# tile.net
KiCad netlist of a schematic drawn in EAGLE
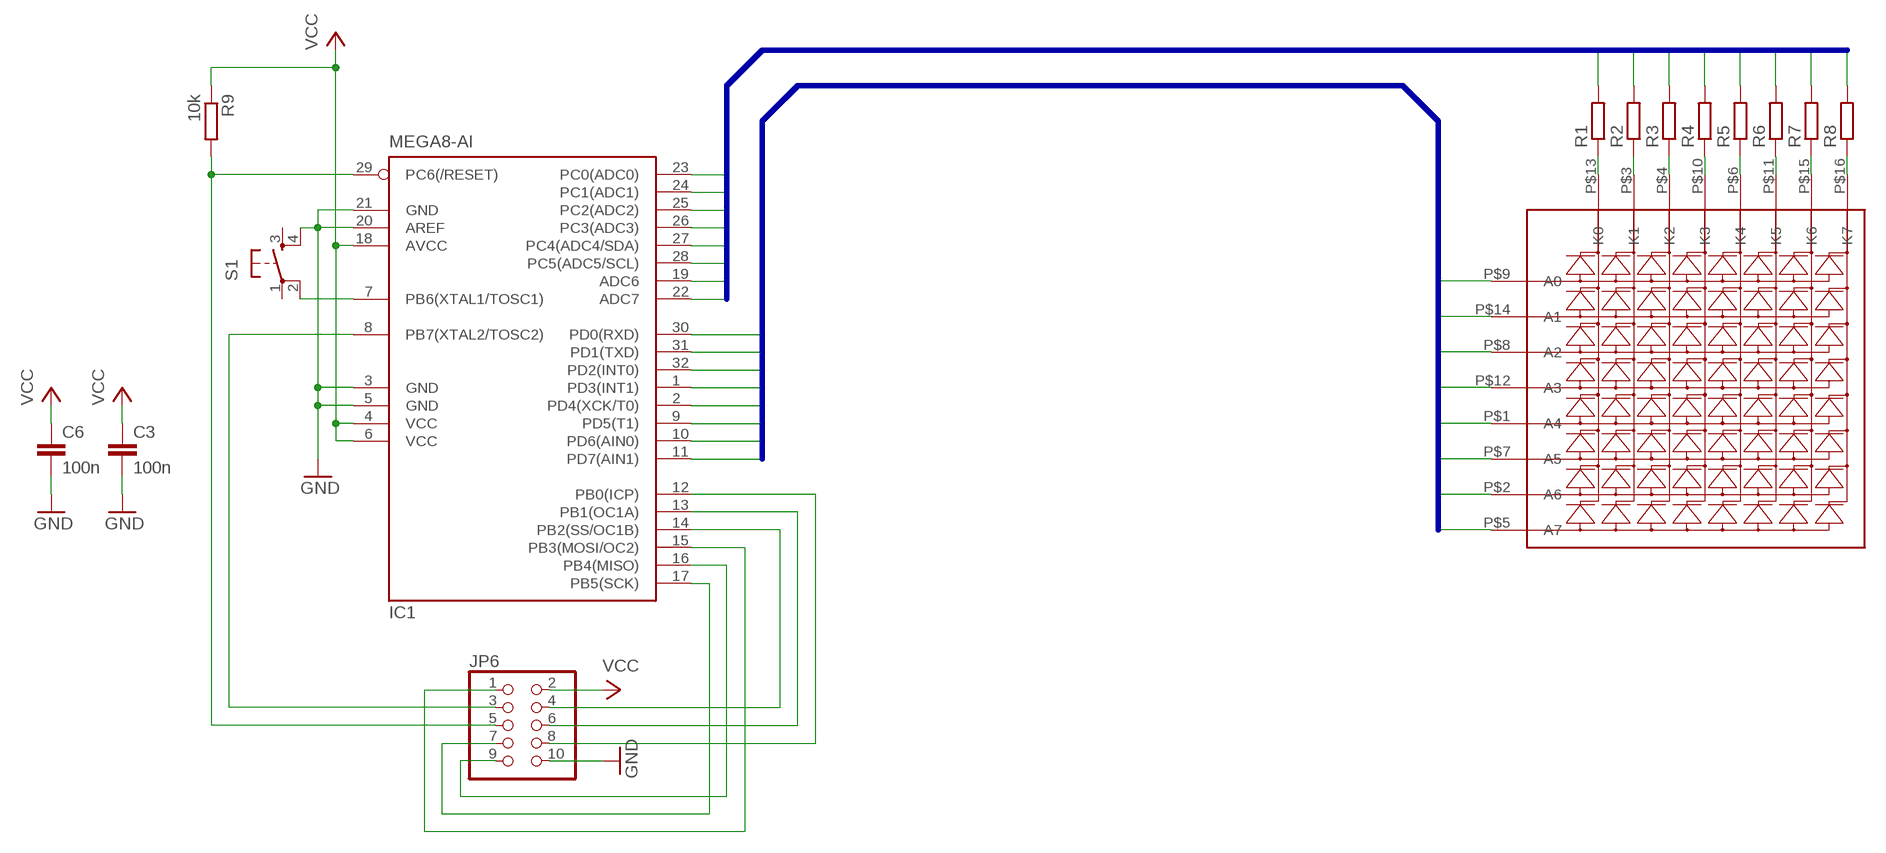
[diagram p0: schematic, sheet 1]
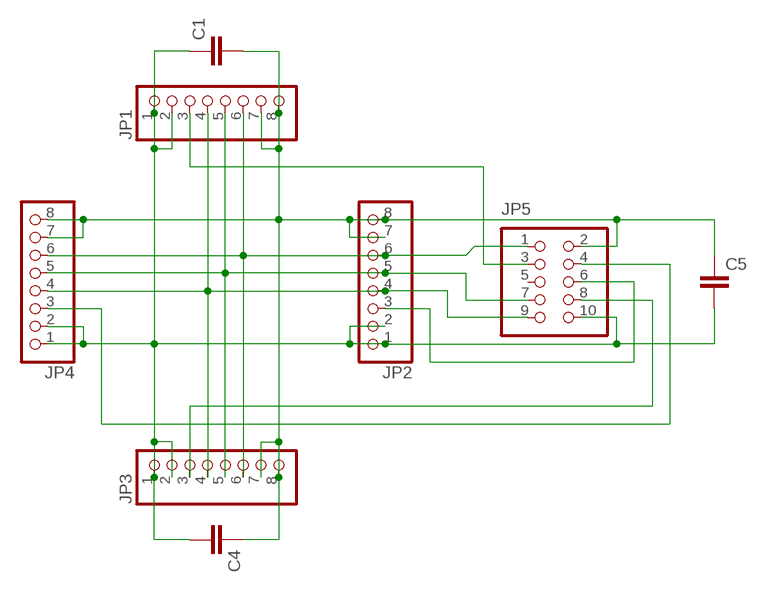
[diagram p1: schematic, sheet 2]

(export (version "E")
  (design (tool "Eeschema 10.0.6"))
  (components
    (comp (ref "C3")
      (value "100n")
      (footprint "eagle-import:C0805")
      (libsource (lib "eagle-import") (part "C-EUC0805"))
    )
    (comp (ref "C6")
      (value "100n")
      (footprint "eagle-import:C0805")
      (libsource (lib "eagle-import") (part "C-EUC0805"))
    )
    (comp (ref "IC1")
      (value "MEGA8-AI")
      (footprint "eagle-import:TQFP32-08")
      (libsource (lib "eagle-import") (part "MEGA8-AI"))
    )
    (comp (ref "JP6")
      (value "PINHD-2X5_2.54")
      (footprint "eagle-import:2X05")
      (libsource (lib "eagle-import") (part "PINHD-2X5_2.54"))
    )
    (comp (ref "R1")
      (value "R-EU_M0805")
      (footprint "eagle-import:M0805")
      (libsource (lib "eagle-import") (part "R-EU_M0805"))
    )
    (comp (ref "R2")
      (value "R-EU_M0805")
      (footprint "eagle-import:M0805")
      (libsource (lib "eagle-import") (part "R-EU_M0805"))
    )
    (comp (ref "R3")
      (value "R-EU_M0805")
      (footprint "eagle-import:M0805")
      (libsource (lib "eagle-import") (part "R-EU_M0805"))
    )
    (comp (ref "R4")
      (value "R-EU_M0805")
      (footprint "eagle-import:M0805")
      (libsource (lib "eagle-import") (part "R-EU_M0805"))
    )
    (comp (ref "R5")
      (value "R-EU_M0805")
      (footprint "eagle-import:M0805")
      (libsource (lib "eagle-import") (part "R-EU_M0805"))
    )
    (comp (ref "R6")
      (value "R-EU_M0805")
      (footprint "eagle-import:M0805")
      (libsource (lib "eagle-import") (part "R-EU_M0805"))
    )
    (comp (ref "R7")
      (value "R-EU_M0805")
      (footprint "eagle-import:M0805")
      (libsource (lib "eagle-import") (part "R-EU_M0805"))
    )
    (comp (ref "R8")
      (value "R-EU_M0805")
      (footprint "eagle-import:M0805")
      (libsource (lib "eagle-import") (part "R-EU_M0805"))
    )
    (comp (ref "R9")
      (value "10k")
      (footprint "eagle-import:M0805")
      (libsource (lib "eagle-import") (part "R-EU_M0805"))
    )
    (comp (ref "S1")
      (value "TAC_SWITCHSMD")
      (footprint "eagle-import:TACTILE_SWITCH_SMD")
      (libsource (lib "eagle-import") (part "TAC_SWITCHSMD"))
    )
    (comp (ref "U$1")
      (value "LED-MATRIX")
      (footprint "eagle-import:LED-MATRIX")
      (libsource (lib "eagle-import") (part "LED-MATRIX"))
    )
    (comp (ref "C1")
      (value "C-EUC0805")
      (footprint "eagle-import:C0805")
      (libsource (lib "eagle-import") (part "C-EUC0805"))
    )
    (comp (ref "C4")
      (value "C-EUC0805")
      (footprint "eagle-import:C0805")
      (libsource (lib "eagle-import") (part "C-EUC0805"))
    )
    (comp (ref "C5")
      (value "C-EUC0805")
      (footprint "eagle-import:C0805")
      (libsource (lib "eagle-import") (part "C-EUC0805"))
    )
    (comp (ref "JP1")
      (value "PINHD-1X8_2.00")
      (footprint "eagle-import:1X08M")
      (libsource (lib "eagle-import") (part "PINHD-1X8_2.00"))
    )
    (comp (ref "JP2")
      (value "PINHD-1X8_2.00")
      (footprint "eagle-import:1X08M")
      (libsource (lib "eagle-import") (part "PINHD-1X8_2.00"))
    )
    (comp (ref "JP3")
      (value "PINHD-1X8_2.00")
      (footprint "eagle-import:1X08M")
      (libsource (lib "eagle-import") (part "PINHD-1X8_2.00"))
    )
    (comp (ref "JP4")
      (value "PINHD-1X8_2.00")
      (footprint "eagle-import:1X08M")
      (libsource (lib "eagle-import") (part "PINHD-1X8_2.00"))
    )
    (comp (ref "JP5")
      (value "PINHD-2X5_2.54")
      (footprint "eagle-import:2X05")
      (libsource (lib "eagle-import") (part "PINHD-2X5_2.54"))
    )
  )
  (nets
    (net (code "1") (name "A0") (class "Default")
      (node (ref "IC1") (pin "30") (pinfunction "PD0(RXD)_30") (pintype "bidirectional"))
      (node (ref "U$1") (pin "P$9") (pinfunction "A0_P$9") (pintype "bidirectional"))
    )
    (net (code "2") (name "A1") (class "Default")
      (node (ref "IC1") (pin "31") (pinfunction "PD1(TXD)_31") (pintype "bidirectional"))
      (node (ref "U$1") (pin "P$14") (pinfunction "A1_P$14") (pintype "bidirectional"))
    )
    (net (code "3") (name "A2") (class "Default")
      (node (ref "IC1") (pin "32") (pinfunction "PD2(INT0)_32") (pintype "bidirectional"))
      (node (ref "U$1") (pin "P$8") (pinfunction "A2_P$8") (pintype "bidirectional"))
    )
    (net (code "4") (name "A3") (class "Default")
      (node (ref "IC1") (pin "1") (pinfunction "PD3(INT1)_1") (pintype "bidirectional"))
      (node (ref "U$1") (pin "P$12") (pinfunction "A3_P$12") (pintype "bidirectional"))
    )
    (net (code "5") (name "A4") (class "Default")
      (node (ref "IC1") (pin "2") (pinfunction "PD4(XCK/T0)_2") (pintype "bidirectional"))
      (node (ref "U$1") (pin "P$1") (pinfunction "A4_P$1") (pintype "bidirectional"))
    )
    (net (code "6") (name "A5") (class "Default")
      (node (ref "IC1") (pin "9") (pinfunction "PD5(T1)_9") (pintype "bidirectional"))
      (node (ref "U$1") (pin "P$7") (pinfunction "A5_P$7") (pintype "bidirectional"))
    )
    (net (code "7") (name "A6") (class "Default")
      (node (ref "IC1") (pin "10") (pinfunction "PD6(AIN0)_10") (pintype "bidirectional"))
      (node (ref "U$1") (pin "P$2") (pinfunction "A6_P$2") (pintype "bidirectional"))
    )
    (net (code "8") (name "A7") (class "Default")
      (node (ref "IC1") (pin "11") (pinfunction "PD7(AIN1)_11") (pintype "bidirectional"))
      (node (ref "U$1") (pin "P$5") (pinfunction "A7_P$5") (pintype "bidirectional"))
    )
    (net (code "9") (name "GND") (class "Default")
      (node (ref "C1") (pin "1") (pinfunction "1_1") (pintype "passive"))
      (node (ref "C3") (pin "2") (pinfunction "2_2") (pintype "passive"))
      (node (ref "C4") (pin "2") (pinfunction "2_2") (pintype "passive"))
      (node (ref "C5") (pin "2") (pinfunction "2_2") (pintype "passive"))
      (node (ref "C6") (pin "2") (pinfunction "2_2") (pintype "passive"))
      (node (ref "IC1") (pin "20") (pinfunction "AREF_20") (pintype "passive"))
      (node (ref "IC1") (pin "21") (pinfunction "GND_21") (pintype "power_in"))
      (node (ref "IC1") (pin "3") (pinfunction "GND_3") (pintype "power_in"))
      (node (ref "IC1") (pin "5") (pinfunction "GND_5") (pintype "power_in"))
      (node (ref "JP1") (pin "1") (pinfunction "1_1") (pintype "passive"))
      (node (ref "JP1") (pin "2") (pinfunction "2_2") (pintype "passive"))
      (node (ref "JP2") (pin "1") (pinfunction "1_1") (pintype "passive"))
      (node (ref "JP2") (pin "2") (pinfunction "2_2") (pintype "passive"))
      (node (ref "JP3") (pin "1") (pinfunction "1_1") (pintype "passive"))
      (node (ref "JP3") (pin "2") (pinfunction "2_2") (pintype "passive"))
      (node (ref "JP4") (pin "1") (pinfunction "1_1") (pintype "passive"))
      (node (ref "JP4") (pin "2") (pinfunction "2_2") (pintype "passive"))
      (node (ref "JP5") (pin "10") (pinfunction "10_10") (pintype "passive"))
      (node (ref "JP6") (pin "10") (pinfunction "10_10") (pintype "passive"))
      (node (ref "S1") (pin "4") (pinfunction "4_4") (pintype "passive"))
    )
    (net (code "10") (name "K0") (class "Default")
      (node (ref "IC1") (pin "23") (pinfunction "PC0(ADC0)_23") (pintype "bidirectional"))
      (node (ref "R1") (pin "2") (pinfunction "2_2") (pintype "passive"))
    )
    (net (code "11") (name "K1") (class "Default")
      (node (ref "IC1") (pin "24") (pinfunction "PC1(ADC1)_24") (pintype "bidirectional"))
      (node (ref "R2") (pin "2") (pinfunction "2_2") (pintype "passive"))
    )
    (net (code "12") (name "K2") (class "Default")
      (node (ref "IC1") (pin "25") (pinfunction "PC2(ADC2)_25") (pintype "bidirectional"))
      (node (ref "R3") (pin "2") (pinfunction "2_2") (pintype "passive"))
    )
    (net (code "13") (name "K3") (class "Default")
      (node (ref "IC1") (pin "26") (pinfunction "PC3(ADC3)_26") (pintype "bidirectional"))
      (node (ref "R4") (pin "2") (pinfunction "2_2") (pintype "passive"))
    )
    (net (code "14") (name "K4") (class "Default")
      (node (ref "IC1") (pin "27") (pinfunction "PC4(ADC4/SDA)_27") (pintype "bidirectional"))
      (node (ref "R5") (pin "2") (pinfunction "2_2") (pintype "passive"))
    )
    (net (code "15") (name "K5") (class "Default")
      (node (ref "IC1") (pin "28") (pinfunction "PC5(ADC5/SCL)_28") (pintype "bidirectional"))
      (node (ref "R6") (pin "2") (pinfunction "2_2") (pintype "passive"))
    )
    (net (code "16") (name "K6") (class "Default")
      (node (ref "IC1") (pin "19") (pinfunction "ADC6_19") (pintype "bidirectional"))
      (node (ref "R7") (pin "2") (pinfunction "2_2") (pintype "passive"))
    )
    (net (code "17") (name "K7") (class "Default")
      (node (ref "IC1") (pin "22") (pinfunction "ADC7_22") (pintype "bidirectional"))
      (node (ref "R8") (pin "2") (pinfunction "2_2") (pintype "passive"))
    )
    (net (code "18") (name "Net-(IC1-PB0(ICP))") (class "Default")
      (node (ref "IC1") (pin "12") (pinfunction "PB0(ICP)_12") (pintype "bidirectional"))
      (node (ref "JP6") (pin "8") (pinfunction "8_8") (pintype "passive"))
    )
    (net (code "19") (name "Net-(IC1-PB1(OC1A))") (class "Default")
      (node (ref "IC1") (pin "13") (pinfunction "PB1(OC1A)_13") (pintype "bidirectional"))
      (node (ref "JP6") (pin "6") (pinfunction "6_6") (pintype "passive"))
    )
    (net (code "20") (name "Net-(IC1-PB2(SS{slash}OC1B))") (class "Default")
      (node (ref "IC1") (pin "14") (pinfunction "PB2(SS/OC1B)_14") (pintype "bidirectional"))
      (node (ref "JP6") (pin "4") (pinfunction "4_4") (pintype "passive"))
    )
    (net (code "21") (name "Net-(IC1-PB3(MOSI{slash}OC2))") (class "Default")
      (node (ref "IC1") (pin "15") (pinfunction "PB3(MOSI/OC2)_15") (pintype "bidirectional"))
      (node (ref "JP6") (pin "1") (pinfunction "1_1") (pintype "passive"))
    )
    (net (code "22") (name "Net-(IC1-PB4(MISO))") (class "Default")
      (node (ref "IC1") (pin "16") (pinfunction "PB4(MISO)_16") (pintype "bidirectional"))
      (node (ref "JP6") (pin "9") (pinfunction "9_9") (pintype "passive"))
    )
    (net (code "23") (name "Net-(IC1-PB5(SCK))") (class "Default")
      (node (ref "IC1") (pin "17") (pinfunction "PB5(SCK)_17") (pintype "bidirectional"))
      (node (ref "JP6") (pin "7") (pinfunction "7_7") (pintype "passive"))
    )
    (net (code "24") (name "Net-(IC1-PB6(XTAL1{slash}TOSC1))") (class "Default")
      (node (ref "IC1") (pin "7") (pinfunction "PB6(XTAL1/TOSC1)_7") (pintype "bidirectional"))
      (node (ref "S1") (pin "2") (pinfunction "2_2") (pintype "passive"))
    )
    (net (code "25") (name "Net-(IC1-PB7(XTAL2{slash}TOSC2))") (class "Default")
      (node (ref "IC1") (pin "8") (pinfunction "PB7(XTAL2/TOSC2)_8") (pintype "bidirectional"))
      (node (ref "JP6") (pin "3") (pinfunction "3_3") (pintype "passive"))
    )
    (net (code "26") (name "Net-(IC1-PC6({slash}RESET))") (class "Default")
      (node (ref "IC1") (pin "29") (pinfunction "PC6(/RESET)_29") (pintype "bidirectional"))
      (node (ref "JP6") (pin "5") (pinfunction "5_5") (pintype "passive"))
      (node (ref "R9") (pin "2") (pinfunction "2_2") (pintype "passive"))
    )
    (net (code "27") (name "Net-(JP1-Pad3)") (class "Default")
      (node (ref "JP1") (pin "3") (pinfunction "3_3") (pintype "passive"))
      (node (ref "JP5") (pin "3") (pinfunction "3_3") (pintype "passive"))
    )
    (net (code "28") (name "Net-(JP1-Pad4)") (class "Default")
      (node (ref "JP1") (pin "4") (pinfunction "4_4") (pintype "passive"))
      (node (ref "JP2") (pin "4") (pinfunction "4_4") (pintype "passive"))
      (node (ref "JP3") (pin "4") (pinfunction "4_4") (pintype "passive"))
      (node (ref "JP4") (pin "4") (pinfunction "4_4") (pintype "passive"))
      (node (ref "JP5") (pin "9") (pinfunction "9_9") (pintype "passive"))
    )
    (net (code "29") (name "Net-(JP1-Pad5)") (class "Default")
      (node (ref "JP1") (pin "5") (pinfunction "5_5") (pintype "passive"))
      (node (ref "JP2") (pin "5") (pinfunction "5_5") (pintype "passive"))
      (node (ref "JP3") (pin "5") (pinfunction "5_5") (pintype "passive"))
      (node (ref "JP4") (pin "5") (pinfunction "5_5") (pintype "passive"))
      (node (ref "JP5") (pin "7") (pinfunction "7_7") (pintype "passive"))
    )
    (net (code "30") (name "Net-(JP1-Pad6)") (class "Default")
      (node (ref "JP1") (pin "6") (pinfunction "6_6") (pintype "passive"))
      (node (ref "JP2") (pin "6") (pinfunction "6_6") (pintype "passive"))
      (node (ref "JP3") (pin "6") (pinfunction "6_6") (pintype "passive"))
      (node (ref "JP4") (pin "6") (pinfunction "6_6") (pintype "passive"))
      (node (ref "JP5") (pin "1") (pinfunction "1_1") (pintype "passive"))
    )
    (net (code "31") (name "Net-(JP2-Pad3)") (class "Default")
      (node (ref "JP2") (pin "3") (pinfunction "3_3") (pintype "passive"))
      (node (ref "JP5") (pin "6") (pinfunction "6_6") (pintype "passive"))
    )
    (net (code "32") (name "Net-(JP3-Pad3)") (class "Default")
      (node (ref "JP3") (pin "3") (pinfunction "3_3") (pintype "passive"))
      (node (ref "JP5") (pin "8") (pinfunction "8_8") (pintype "passive"))
    )
    (net (code "33") (name "Net-(JP4-Pad3)") (class "Default")
      (node (ref "JP4") (pin "3") (pinfunction "3_3") (pintype "passive"))
      (node (ref "JP5") (pin "4") (pinfunction "4_4") (pintype "passive"))
    )
    (net (code "34") (name "Net-(U$1-K0)") (class "Default")
      (node (ref "R1") (pin "1") (pinfunction "1_1") (pintype "passive"))
      (node (ref "U$1") (pin "P$13") (pinfunction "K0_P$13") (pintype "bidirectional"))
    )
    (net (code "35") (name "Net-(U$1-K1)") (class "Default")
      (node (ref "R2") (pin "1") (pinfunction "1_1") (pintype "passive"))
      (node (ref "U$1") (pin "P$3") (pinfunction "K1_P$3") (pintype "bidirectional"))
    )
    (net (code "36") (name "Net-(U$1-K2)") (class "Default")
      (node (ref "R3") (pin "1") (pinfunction "1_1") (pintype "passive"))
      (node (ref "U$1") (pin "P$4") (pinfunction "K2_P$4") (pintype "bidirectional"))
    )
    (net (code "37") (name "Net-(U$1-K3)") (class "Default")
      (node (ref "R4") (pin "1") (pinfunction "1_1") (pintype "passive"))
      (node (ref "U$1") (pin "P$10") (pinfunction "K3_P$10") (pintype "bidirectional"))
    )
    (net (code "38") (name "Net-(U$1-K4)") (class "Default")
      (node (ref "R5") (pin "1") (pinfunction "1_1") (pintype "passive"))
      (node (ref "U$1") (pin "P$6") (pinfunction "K4_P$6") (pintype "bidirectional"))
    )
    (net (code "39") (name "Net-(U$1-K5)") (class "Default")
      (node (ref "R6") (pin "1") (pinfunction "1_1") (pintype "passive"))
      (node (ref "U$1") (pin "P$11") (pinfunction "K5_P$11") (pintype "bidirectional"))
    )
    (net (code "40") (name "Net-(U$1-K6)") (class "Default")
      (node (ref "R7") (pin "1") (pinfunction "1_1") (pintype "passive"))
      (node (ref "U$1") (pin "P$15") (pinfunction "K6_P$15") (pintype "bidirectional"))
    )
    (net (code "41") (name "Net-(U$1-K7)") (class "Default")
      (node (ref "R8") (pin "1") (pinfunction "1_1") (pintype "passive"))
      (node (ref "U$1") (pin "P$16") (pinfunction "K7_P$16") (pintype "bidirectional"))
    )
    (net (code "42") (name "VCC") (class "Default")
      (node (ref "C1") (pin "2") (pinfunction "2_2") (pintype "passive"))
      (node (ref "C3") (pin "1") (pinfunction "1_1") (pintype "passive"))
      (node (ref "C4") (pin "1") (pinfunction "1_1") (pintype "passive"))
      (node (ref "C5") (pin "1") (pinfunction "1_1") (pintype "passive"))
      (node (ref "C6") (pin "1") (pinfunction "1_1") (pintype "passive"))
      (node (ref "IC1") (pin "18") (pinfunction "AVCC_18") (pintype "power_in"))
      (node (ref "IC1") (pin "4") (pinfunction "VCC_4") (pintype "power_in"))
      (node (ref "IC1") (pin "6") (pinfunction "VCC_6") (pintype "power_in"))
      (node (ref "JP1") (pin "7") (pinfunction "7_7") (pintype "passive"))
      (node (ref "JP1") (pin "8") (pinfunction "8_8") (pintype "passive"))
      (node (ref "JP2") (pin "7") (pinfunction "7_7") (pintype "passive"))
      (node (ref "JP2") (pin "8") (pinfunction "8_8") (pintype "passive"))
      (node (ref "JP3") (pin "7") (pinfunction "7_7") (pintype "passive"))
      (node (ref "JP3") (pin "8") (pinfunction "8_8") (pintype "passive"))
      (node (ref "JP4") (pin "7") (pinfunction "7_7") (pintype "passive"))
      (node (ref "JP4") (pin "8") (pinfunction "8_8") (pintype "passive"))
      (node (ref "JP5") (pin "2") (pinfunction "2_2") (pintype "passive"))
      (node (ref "JP6") (pin "2") (pinfunction "2_2") (pintype "passive"))
      (node (ref "R9") (pin "1") (pinfunction "1_1") (pintype "passive"))
    )
    (net (code "43") (name "unconnected-(JP5-Pad5)") (class "Default")
      (node (ref "JP5") (pin "5") (pinfunction "5_5") (pintype "passive"))
    )
    (net (code "44") (name "unconnected-(S1-Pad1)") (class "Default")
      (node (ref "S1") (pin "1") (pinfunction "1_1") (pintype "passive"))
    )
    (net (code "45") (name "unconnected-(S1-Pad3)") (class "Default")
      (node (ref "S1") (pin "3") (pinfunction "3_3") (pintype "passive"))
    )
  )
)
